# fab.net
KiCad netlist of a schematic drawn in Altium Designer
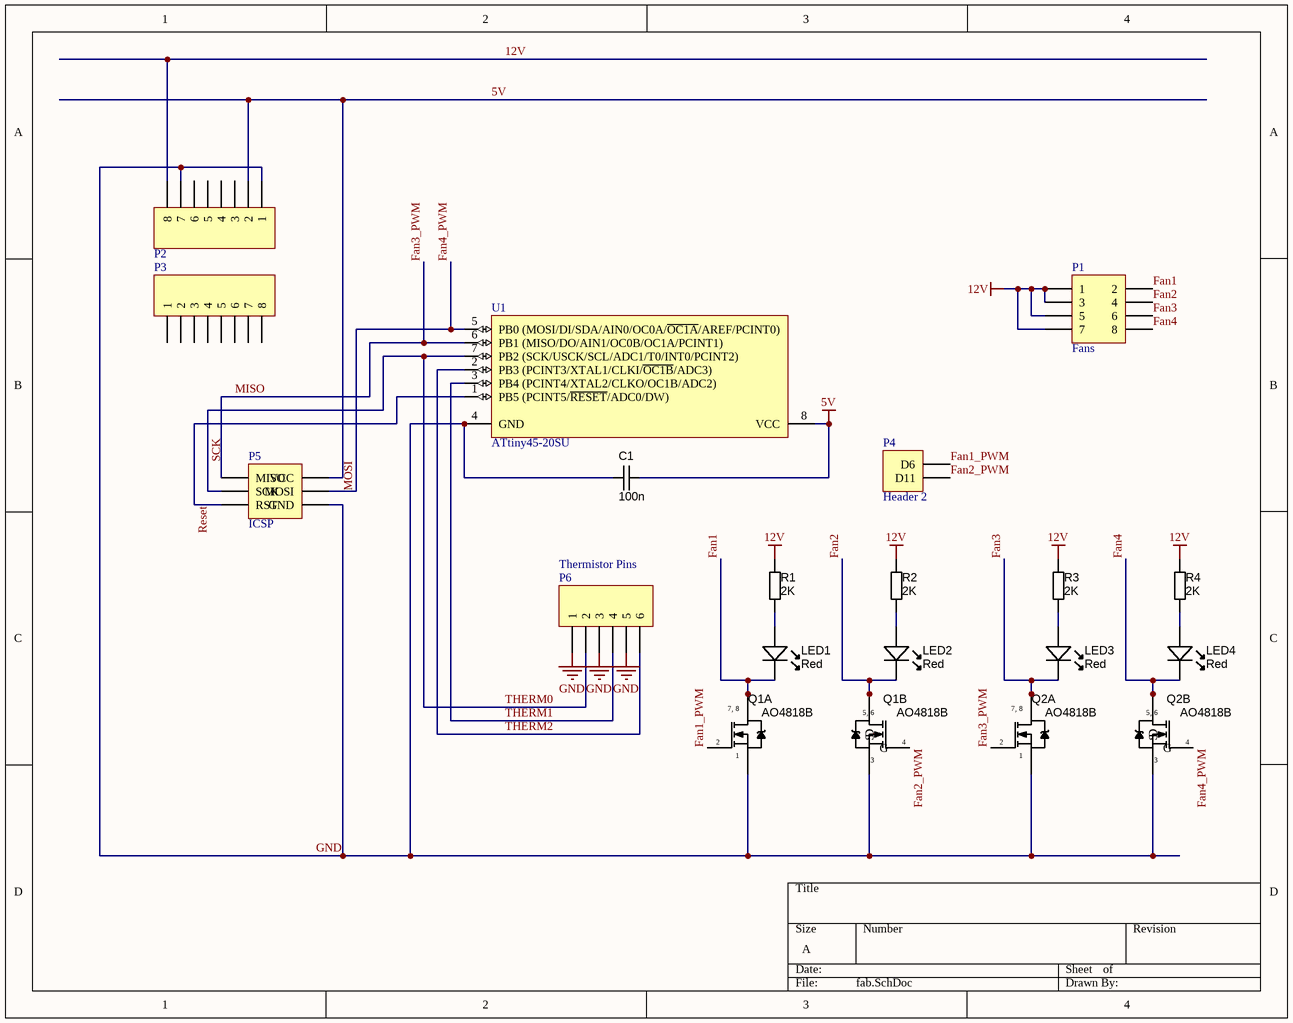
[diagram p0: fab.SchDoc]

(export (version "E")
  (design (tool "Eeschema 10.0.6"))
  (components
    (comp (ref "C1")
      (value "100n")
      (footprint "CAPC1005X55N")
      (description "Capacitor SMD Cer 100nF 10% 16V X5R 0402")
      (fields (field (name "TOLERANCE") "±10%"))
      (libsource (lib "PBL - Capacitors") (part "CAPC_100n_0402_X5R_16V_10%"))
    )
    (comp (ref "LED1")
      (value "Red")
      (footprint "LED-0603-RED")
      (description "LED 0603 SMD Hyper Red 630nm 220mcd 20mA")
      (libsource (lib "PBL - Light Sources") (part "LED_SMD_Red_0603_220mcd"))
    )
    (comp (ref "LED2")
      (value "Red")
      (footprint "LED-0603-RED")
      (description "LED 0603 SMD Hyper Red 630nm 220mcd 20mA")
      (libsource (lib "PBL - Light Sources") (part "LED_SMD_Red_0603_220mcd"))
    )
    (comp (ref "LED3")
      (value "Red")
      (footprint "LED-0603-RED")
      (description "LED 0603 SMD Hyper Red 630nm 220mcd 20mA")
      (libsource (lib "PBL - Light Sources") (part "LED_SMD_Red_0603_220mcd"))
    )
    (comp (ref "LED4")
      (value "Red")
      (footprint "LED-0603-RED")
      (description "LED 0603 SMD Hyper Red 630nm 220mcd 20mA")
      (libsource (lib "PBL - Light Sources") (part "LED_SMD_Red_0603_220mcd"))
    )
    (comp (ref "P1")
      (value "Fans")
      (footprint "HDR2X4")
      (description "Header, 4-Pin, Dual row")
      (fields (field (name "PUBLISHER") "Altium Limited"))
      (libsource (lib "Miscellaneous Connectors") (part "Header 4X2"))
    )
    (comp (ref "P2")
      (value "Header 8")
      (footprint "HDR1X8")
      (description "Header, 8-Pin")
      (fields (field (name "PUBLISHER") "Altium Limited"))
      (libsource (lib "Miscellaneous Connectors") (part "Header 8"))
    )
    (comp (ref "P3")
      (value "Header 8")
      (footprint "HDR1X8")
      (description "Header, 8-Pin")
      (fields (field (name "PUBLISHER") "Altium Limited"))
      (libsource (lib "") (part "Header 8_1"))
    )
    (comp (ref "P4")
      (value "Header 2")
      (footprint "HDR1X2")
      (description "Header, 2-Pin")
      (fields (field (name "PUBLISHER") "Altium Limited"))
      (libsource (lib "Miscellaneous Connectors") (part "Header 2"))
    )
    (comp (ref "P5")
      (value "ICSP")
      (footprint "ICSP Pads")
      (description "Header, 3-Pin, Dual row")
      (fields (field (name "PUBLISHER") "Altium Limited"))
      (libsource (lib "Miscellaneous Connectors") (part "Header 3X2"))
    )
    (comp (ref "P6")
      (value "Thermistor Pins")
      (footprint "HDR1X6")
      (description "Header, 6-Pin")
      (fields (field (name "PUBLISHER") "Altium Limited"))
      (libsource (lib "Miscellaneous Connectors") (part "Header 6"))
    )
    (comp (ref "Q1")
      (value "MOSFET_AO4818B")
      (footprint "SOIC127P600X175-8AN")
      (description "MOSFET Dual-Channel 30V 8.5A SOIC-8 SMD")
      (fields (field (name "MANUFACTURER PART NUMBER 1") "AO4818B"))
      (libsource (lib "") (part "MOSFET_AO4818B_1"))
    )
    (comp (ref "Q2")
      (value "MOSFET_AO4818B")
      (footprint "SOIC127P600X175-8AN")
      (description "MOSFET Dual-Channel 30V 8.5A SOIC-8 SMD")
      (fields (field (name "MANUFACTURER PART NUMBER 1") "AO4818B"))
      (libsource (lib "PBL - Transistors") (part "MOSFET_AO4818B"))
    )
    (comp (ref "R1")
      (value "2K")
      (footprint "RESC1608X55N")
      (description "Resistor SMD chip 330 Ohm 0.1W 5% 0603")
      (fields (field (name "TOLERANCE") "±5%") (field (name "Comment") "Thick Film"))
      (libsource (lib "PBL - Resistors") (part "RES_330R_0603_5%"))
    )
    (comp (ref "R2")
      (value "2K")
      (footprint "RESC1608X55N")
      (description "Resistor SMD chip 330 Ohm 0.1W 5% 0603")
      (fields (field (name "TOLERANCE") "±5%") (field (name "Comment") "Thick Film"))
      (libsource (lib "PBL - Resistors") (part "RES_330R_0603_5%"))
    )
    (comp (ref "R3")
      (value "2K")
      (footprint "RESC1608X55N")
      (description "Resistor SMD chip 330 Ohm 0.1W 5% 0603")
      (fields (field (name "TOLERANCE") "±5%") (field (name "Comment") "Thick Film"))
      (libsource (lib "PBL - Resistors") (part "RES_330R_0603_5%"))
    )
    (comp (ref "R4")
      (value "2K")
      (footprint "RESC1608X55N")
      (description "Resistor SMD chip 330 Ohm 0.1W 5% 0603")
      (fields (field (name "TOLERANCE") "±5%") (field (name "Comment") "Thick Film"))
      (libsource (lib "PBL - Resistors") (part "RES_330R_0603_5%"))
    )
    (comp (ref "U1")
      (value "ATtiny45-20SU")
      (footprint "8S2_N")
      (libsource (lib "Atmel Microcontroller tinyAVR") (part "ATtiny45-20SU"))
    )
  )
  (nets
    (net (code "1") (name "/Fan1") (class "Default")
      (node (ref "LED1") (pin "K") (pinfunction "K_K") (pintype "passive"))
      (node (ref "P1") (pin "2") (pinfunction "2_2") (pintype "passive"))
      (node (ref "Q1") (pin "7") (pinfunction "D_7") (pintype "passive"))
      (node (ref "Q1") (pin "8") (pinfunction "D_8") (pintype "passive"))
    )
    (net (code "2") (name "/Fan1_PWM") (class "Default")
      (node (ref "P4") (pin "2") (pinfunction "D6_2") (pintype "passive"))
      (node (ref "Q1") (pin "2") (pinfunction "G_2") (pintype "passive"))
    )
    (net (code "3") (name "/Fan2") (class "Default")
      (node (ref "LED2") (pin "K") (pinfunction "K_K") (pintype "passive"))
      (node (ref "P1") (pin "4") (pinfunction "4_4") (pintype "passive"))
      (node (ref "Q1") (pin "5") (pinfunction "D_5") (pintype "passive"))
      (node (ref "Q1") (pin "6") (pinfunction "D_6") (pintype "passive"))
    )
    (net (code "4") (name "/Fan2_PWM") (class "Default")
      (node (ref "P4") (pin "1") (pinfunction "D11_1") (pintype "passive"))
      (node (ref "Q1") (pin "4") (pinfunction "G_4") (pintype "passive"))
    )
    (net (code "5") (name "/Fan3") (class "Default")
      (node (ref "LED3") (pin "K") (pinfunction "K_K") (pintype "passive"))
      (node (ref "P1") (pin "6") (pinfunction "6_6") (pintype "passive"))
      (node (ref "Q2") (pin "7") (pinfunction "D_7") (pintype "passive"))
      (node (ref "Q2") (pin "8") (pinfunction "D_8") (pintype "passive"))
    )
    (net (code "6") (name "/Fan3_PWM") (class "Default")
      (node (ref "P5") (pin "0") (pinfunction "MISO_0") (pintype "passive"))
      (node (ref "Q2") (pin "2") (pinfunction "G_2") (pintype "passive"))
      (node (ref "U1") (pin "6") (pinfunction "PB1_(MISO/DO/AIN1/OC0B/OC1A/PCINT1)_6") (pintype "bidirectional"))
    )
    (net (code "7") (name "/Fan4") (class "Default")
      (node (ref "LED4") (pin "K") (pinfunction "K_K") (pintype "passive"))
      (node (ref "P1") (pin "8") (pinfunction "8_8") (pintype "passive"))
      (node (ref "Q2") (pin "5") (pinfunction "D_5") (pintype "passive"))
      (node (ref "Q2") (pin "6") (pinfunction "D_6") (pintype "passive"))
    )
    (net (code "8") (name "/Fan4_PWM") (class "Default")
      (node (ref "P5") (pin "3") (pinfunction "MOSI_3") (pintype "passive"))
      (node (ref "Q2") (pin "4") (pinfunction "G_4") (pintype "passive"))
      (node (ref "U1") (pin "5") (pinfunction "PB0_(MOSI/DI/SDA/AIN0/OC0A/~{OC1A}/AREF/PCINT0)_5") (pintype "bidirectional"))
    )
    (net (code "9") (name "/Reset") (class "Default")
      (node (ref "P5") (pin "4") (pinfunction "RST_4") (pintype "passive"))
      (node (ref "U1") (pin "1") (pinfunction "PB5_(PCINT5/~{RESET}/ADC0/DW)_1") (pintype "bidirectional"))
    )
    (net (code "10") (name "/SCK") (class "Default")
      (node (ref "P5") (pin "2") (pinfunction "SCK_2") (pintype "passive"))
      (node (ref "P6") (pin "2") (pinfunction "2_2") (pintype "passive"))
      (node (ref "U1") (pin "7") (pinfunction "PB2_(SCK/USCK/SCL/ADC1/T0/INT0/PCINT2)_7") (pintype "bidirectional"))
    )
    (net (code "11") (name "/THERM1") (class "Default")
      (node (ref "P6") (pin "4") (pinfunction "4_4") (pintype "passive"))
      (node (ref "U1") (pin "3") (pinfunction "PB4_(PCINT4/XTAL2/CLKO/OC1B/ADC2)_3") (pintype "bidirectional"))
    )
    (net (code "12") (name "/THERM2") (class "Default")
      (node (ref "P6") (pin "6") (pinfunction "6_6") (pintype "passive"))
      (node (ref "U1") (pin "2") (pinfunction "PB3_(PCINT3/XTAL1/CLKI/~{OC1B}/ADC3)_2") (pintype "bidirectional"))
    )
    (net (code "13") (name "5V") (class "Default")
      (node (ref "C1") (pin "2") (pintype "passive"))
      (node (ref "P2") (pin "2") (pinfunction "2_2") (pintype "passive"))
      (node (ref "P5") (pin "1") (pinfunction "VCC_1") (pintype "passive"))
      (node (ref "U1") (pin "8") (pinfunction "VCC_8") (pintype "power_in"))
    )
    (net (code "14") (name "12V") (class "Default")
      (node (ref "P1") (pin "1") (pinfunction "1_1") (pintype "passive"))
      (node (ref "P1") (pin "3") (pinfunction "3_3") (pintype "passive"))
      (node (ref "P1") (pin "5") (pinfunction "5_5") (pintype "passive"))
      (node (ref "P1") (pin "7") (pinfunction "7_7") (pintype "passive"))
      (node (ref "P2") (pin "8") (pinfunction "8_8") (pintype "passive"))
      (node (ref "R1") (pin "1") (pinfunction "1_1") (pintype "passive"))
      (node (ref "R2") (pin "1") (pinfunction "1_1") (pintype "passive"))
      (node (ref "R3") (pin "1") (pinfunction "1_1") (pintype "passive"))
      (node (ref "R4") (pin "1") (pinfunction "1_1") (pintype "passive"))
    )
    (net (code "15") (name "GND") (class "Default")
      (node (ref "C1") (pin "1") (pintype "passive"))
      (node (ref "P2") (pin "1") (pinfunction "1_1") (pintype "passive"))
      (node (ref "P2") (pin "7") (pinfunction "7_7") (pintype "passive"))
      (node (ref "P5") (pin "5") (pinfunction "GND_5") (pintype "passive"))
      (node (ref "P6") (pin "1") (pinfunction "1_1") (pintype "passive"))
      (node (ref "P6") (pin "3") (pinfunction "3_3") (pintype "passive"))
      (node (ref "P6") (pin "5") (pinfunction "5_5") (pintype "passive"))
      (node (ref "Q1") (pin "1") (pinfunction "S_1") (pintype "passive"))
      (node (ref "Q1") (pin "3") (pinfunction "S_3") (pintype "passive"))
      (node (ref "Q2") (pin "1") (pinfunction "S_1") (pintype "passive"))
      (node (ref "Q2") (pin "3") (pinfunction "S_3") (pintype "passive"))
      (node (ref "U1") (pin "4") (pinfunction "GND_4") (pintype "power_in"))
    )
    (net (code "16") (name "Net-(LED1-PadA)") (class "Default")
      (node (ref "LED1") (pin "A") (pinfunction "A_A") (pintype "passive"))
      (node (ref "R1") (pin "2") (pinfunction "2_2") (pintype "passive"))
    )
    (net (code "17") (name "Net-(LED2-PadA)") (class "Default")
      (node (ref "LED2") (pin "A") (pinfunction "A_A") (pintype "passive"))
      (node (ref "R2") (pin "2") (pinfunction "2_2") (pintype "passive"))
    )
    (net (code "18") (name "Net-(LED3-PadA)") (class "Default")
      (node (ref "LED3") (pin "A") (pinfunction "A_A") (pintype "passive"))
      (node (ref "R3") (pin "2") (pinfunction "2_2") (pintype "passive"))
    )
    (net (code "19") (name "Net-(LED4-PadA)") (class "Default")
      (node (ref "LED4") (pin "A") (pinfunction "A_A") (pintype "passive"))
      (node (ref "R4") (pin "2") (pinfunction "2_2") (pintype "passive"))
    )
    (net (code "20") (name "unconnected-(P2-Pad3)") (class "Default")
      (node (ref "P2") (pin "3") (pinfunction "3_3") (pintype "passive"))
    )
    (net (code "21") (name "unconnected-(P2-Pad4)") (class "Default")
      (node (ref "P2") (pin "4") (pinfunction "4_4") (pintype "passive"))
    )
    (net (code "22") (name "unconnected-(P2-Pad5)") (class "Default")
      (node (ref "P2") (pin "5") (pinfunction "5_5") (pintype "passive"))
    )
    (net (code "23") (name "unconnected-(P2-Pad6)") (class "Default")
      (node (ref "P2") (pin "6") (pinfunction "6_6") (pintype "passive"))
    )
    (net (code "24") (name "unconnected-(P3-Pad1)") (class "Default")
      (node (ref "P3") (pin "1") (pinfunction "1_1") (pintype "passive"))
    )
    (net (code "25") (name "unconnected-(P3-Pad2)") (class "Default")
      (node (ref "P3") (pin "2") (pinfunction "2_2") (pintype "passive"))
    )
    (net (code "26") (name "unconnected-(P3-Pad3)") (class "Default")
      (node (ref "P3") (pin "3") (pinfunction "3_3") (pintype "passive"))
    )
    (net (code "27") (name "unconnected-(P3-Pad4)") (class "Default")
      (node (ref "P3") (pin "4") (pinfunction "4_4") (pintype "passive"))
    )
    (net (code "28") (name "unconnected-(P3-Pad5)") (class "Default")
      (node (ref "P3") (pin "5") (pinfunction "5_5") (pintype "passive"))
    )
    (net (code "29") (name "unconnected-(P3-Pad6)") (class "Default")
      (node (ref "P3") (pin "6") (pinfunction "6_6") (pintype "passive"))
    )
    (net (code "30") (name "unconnected-(P3-Pad7)") (class "Default")
      (node (ref "P3") (pin "7") (pinfunction "7_7") (pintype "passive"))
    )
    (net (code "31") (name "unconnected-(P3-Pad8)") (class "Default")
      (node (ref "P3") (pin "8") (pinfunction "8_8") (pintype "passive"))
    )
  )
)
